# MEM.net
KiCad netlist of a schematic drawn in Altium Designer
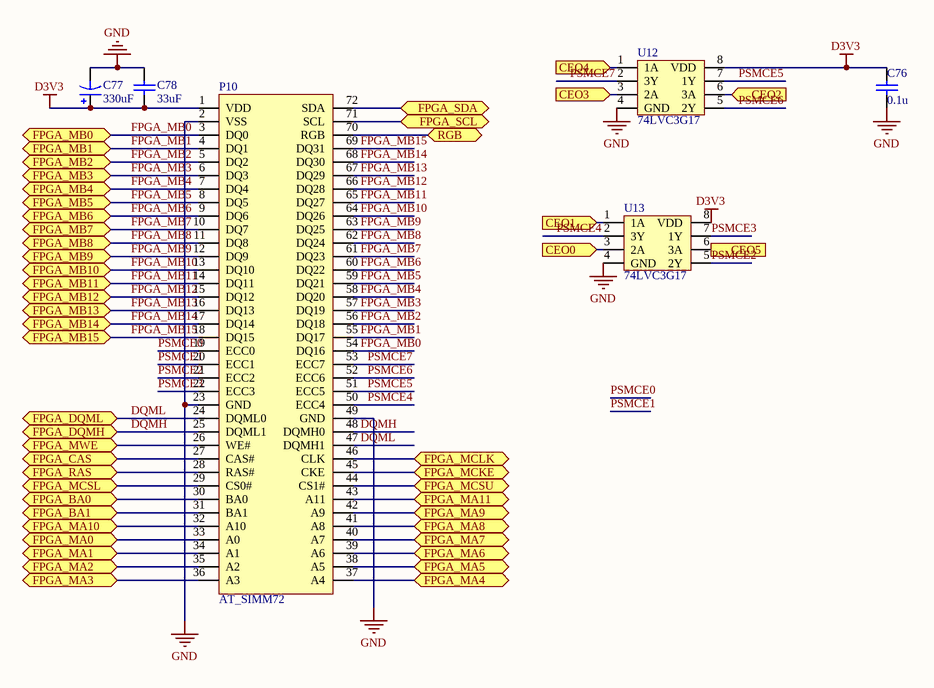
[diagram p0: MEM.SchDoc]

(export (version "E")
  (design (tool "Eeschema 10.0.6"))
  (components
    (comp (ref "C76")
      (value "0.1u")
      (footprint "0603C")
      (description "Capacitor")
      (fields (field (name "Comment") "Cap") (field (name "PUBLISHER") "Altium Limited"))
      (libsource (lib "Miscellaneous Devices") (part "Cap"))
    )
    (comp (ref "C77")
      (value "330uF")
      (footprint "TanCap-1210")
      (description "Polarized Capacitor (Radial)")
      (fields (field (name "Comment") "330u") (field (name "PUBLISHER") "Altium Limited"))
      (libsource (lib "Miscellaneous Devices") (part "Cap Pol1"))
    )
    (comp (ref "C78")
      (value "33uF")
      (footprint "0603C")
      (description "Ceramic Capacitor 0603")
      (fields (field (name "Comment") "106") (field (name "PUBLISHER") "Altium Limited"))
      (libsource (lib "Miscellaneous Devices") (part "Cap"))
    )
    (comp (ref "P10")
      (value "AT_SIMM72")
      (footprint "ATSIMM72")
      (libsource (lib "RV_AT_Ports") (part "AT_SIMM72"))
    )
    (comp (ref "U12")
      (value "74LVC3G17")
      (footprint "TSSOP-8N_3x3")
      (libsource (lib "74xLogic") (part "74LVC3G17"))
    )
    (comp (ref "U13")
      (value "74LVC3G17")
      (footprint "TSSOP-8N_3x3")
      (libsource (lib "74xLogic") (part "74LVC3G17"))
    )
  )
  (nets
    (net (code "1") (name "/CEO0") (class "Default")
      (node (ref "U13") (pin "3") (pinfunction "2A_3") (pintype "passive"))
    )
    (net (code "2") (name "/CEO1") (class "Default")
      (node (ref "U13") (pin "1") (pinfunction "1A_1") (pintype "passive"))
    )
    (net (code "3") (name "/CEO2") (class "Default")
      (node (ref "U12") (pin "6") (pinfunction "3A_6") (pintype "passive"))
    )
    (net (code "4") (name "/CEO3") (class "Default")
      (node (ref "U12") (pin "3") (pinfunction "2A_3") (pintype "passive"))
    )
    (net (code "5") (name "/CEO4") (class "Default")
      (node (ref "U12") (pin "1") (pinfunction "1A_1") (pintype "passive"))
    )
    (net (code "6") (name "/CEO5") (class "Default")
      (node (ref "U13") (pin "6") (pinfunction "3A_6") (pintype "passive"))
    )
    (net (code "7") (name "/DQMH") (class "Default")
      (node (ref "P10") (pin "25") (pinfunction "DQML1_25") (pintype "passive"))
      (node (ref "P10") (pin "48") (pinfunction "DQMH0_48") (pintype "passive"))
    )
    (net (code "8") (name "/DQML") (class "Default")
      (node (ref "P10") (pin "24") (pinfunction "DQML0_24") (pintype "passive"))
      (node (ref "P10") (pin "47") (pinfunction "DQMH1_47") (pintype "passive"))
    )
    (net (code "9") (name "/FPGA_BA0") (class "Default")
      (node (ref "P10") (pin "30") (pinfunction "BA0_30") (pintype "passive"))
    )
    (net (code "10") (name "/FPGA_BA1") (class "Default")
      (node (ref "P10") (pin "31") (pinfunction "BA1_31") (pintype "passive"))
    )
    (net (code "11") (name "/FPGA_CAS") (class "Default")
      (node (ref "P10") (pin "27") (pinfunction "CAS#_27") (pintype "passive"))
    )
    (net (code "12") (name "/FPGA_MA0") (class "Default")
      (node (ref "P10") (pin "33") (pinfunction "A0_33") (pintype "passive"))
    )
    (net (code "13") (name "/FPGA_MA1") (class "Default")
      (node (ref "P10") (pin "34") (pinfunction "A1_34") (pintype "passive"))
    )
    (net (code "14") (name "/FPGA_MA2") (class "Default")
      (node (ref "P10") (pin "35") (pinfunction "A2_35") (pintype "passive"))
    )
    (net (code "15") (name "/FPGA_MA3") (class "Default")
      (node (ref "P10") (pin "36") (pinfunction "A3_36") (pintype "passive"))
    )
    (net (code "16") (name "/FPGA_MA4") (class "Default")
      (node (ref "P10") (pin "37") (pinfunction "A4_37") (pintype "passive"))
    )
    (net (code "17") (name "/FPGA_MA5") (class "Default")
      (node (ref "P10") (pin "38") (pinfunction "A5_38") (pintype "passive"))
    )
    (net (code "18") (name "/FPGA_MA6") (class "Default")
      (node (ref "P10") (pin "39") (pinfunction "A6_39") (pintype "passive"))
    )
    (net (code "19") (name "/FPGA_MA7") (class "Default")
      (node (ref "P10") (pin "40") (pinfunction "A7_40") (pintype "passive"))
    )
    (net (code "20") (name "/FPGA_MA8") (class "Default")
      (node (ref "P10") (pin "41") (pinfunction "A8_41") (pintype "passive"))
    )
    (net (code "21") (name "/FPGA_MA9") (class "Default")
      (node (ref "P10") (pin "42") (pinfunction "A9_42") (pintype "passive"))
    )
    (net (code "22") (name "/FPGA_MA10") (class "Default")
      (node (ref "P10") (pin "32") (pinfunction "A10_32") (pintype "passive"))
    )
    (net (code "23") (name "/FPGA_MA11") (class "Default")
      (node (ref "P10") (pin "43") (pinfunction "A11_43") (pintype "passive"))
    )
    (net (code "24") (name "/FPGA_MB0") (class "Default")
      (node (ref "P10") (pin "3") (pinfunction "DQ0_3") (pintype "passive"))
      (node (ref "P10") (pin "54") (pinfunction "DQ16_54") (pintype "passive"))
    )
    (net (code "25") (name "/FPGA_MB1") (class "Default")
      (node (ref "P10") (pin "4") (pinfunction "DQ1_4") (pintype "passive"))
      (node (ref "P10") (pin "55") (pinfunction "DQ17_55") (pintype "passive"))
    )
    (net (code "26") (name "/FPGA_MB2") (class "Default")
      (node (ref "P10") (pin "5") (pinfunction "DQ2_5") (pintype "passive"))
      (node (ref "P10") (pin "56") (pinfunction "DQ18_56") (pintype "passive"))
    )
    (net (code "27") (name "/FPGA_MB3") (class "Default")
      (node (ref "P10") (pin "57") (pinfunction "DQ19_57") (pintype "passive"))
      (node (ref "P10") (pin "6") (pinfunction "DQ3_6") (pintype "passive"))
    )
    (net (code "28") (name "/FPGA_MB4") (class "Default")
      (node (ref "P10") (pin "58") (pinfunction "DQ20_58") (pintype "passive"))
      (node (ref "P10") (pin "7") (pinfunction "DQ4_7") (pintype "passive"))
    )
    (net (code "29") (name "/FPGA_MB5") (class "Default")
      (node (ref "P10") (pin "59") (pinfunction "DQ21_59") (pintype "passive"))
      (node (ref "P10") (pin "8") (pinfunction "DQ5_8") (pintype "passive"))
    )
    (net (code "30") (name "/FPGA_MB6") (class "Default")
      (node (ref "P10") (pin "60") (pinfunction "DQ22_60") (pintype "passive"))
      (node (ref "P10") (pin "9") (pinfunction "DQ6_9") (pintype "passive"))
    )
    (net (code "31") (name "/FPGA_MB7") (class "Default")
      (node (ref "P10") (pin "10") (pinfunction "DQ7_10") (pintype "passive"))
      (node (ref "P10") (pin "61") (pinfunction "DQ23_61") (pintype "passive"))
    )
    (net (code "32") (name "/FPGA_MB8") (class "Default")
      (node (ref "P10") (pin "11") (pinfunction "DQ8_11") (pintype "passive"))
      (node (ref "P10") (pin "62") (pinfunction "DQ24_62") (pintype "passive"))
    )
    (net (code "33") (name "/FPGA_MB9") (class "Default")
      (node (ref "P10") (pin "12") (pinfunction "DQ9_12") (pintype "passive"))
      (node (ref "P10") (pin "63") (pinfunction "DQ25_63") (pintype "passive"))
    )
    (net (code "34") (name "/FPGA_MB10") (class "Default")
      (node (ref "P10") (pin "13") (pinfunction "DQ10_13") (pintype "passive"))
      (node (ref "P10") (pin "64") (pinfunction "DQ26_64") (pintype "passive"))
    )
    (net (code "35") (name "/FPGA_MB11") (class "Default")
      (node (ref "P10") (pin "14") (pinfunction "DQ11_14") (pintype "passive"))
      (node (ref "P10") (pin "65") (pinfunction "DQ27_65") (pintype "passive"))
    )
    (net (code "36") (name "/FPGA_MB12") (class "Default")
      (node (ref "P10") (pin "15") (pinfunction "DQ12_15") (pintype "passive"))
      (node (ref "P10") (pin "66") (pinfunction "DQ28_66") (pintype "passive"))
    )
    (net (code "37") (name "/FPGA_MB13") (class "Default")
      (node (ref "P10") (pin "16") (pinfunction "DQ13_16") (pintype "passive"))
      (node (ref "P10") (pin "67") (pinfunction "DQ29_67") (pintype "passive"))
    )
    (net (code "38") (name "/FPGA_MB14") (class "Default")
      (node (ref "P10") (pin "17") (pinfunction "DQ14_17") (pintype "passive"))
      (node (ref "P10") (pin "68") (pinfunction "DQ30_68") (pintype "passive"))
    )
    (net (code "39") (name "/FPGA_MB15") (class "Default")
      (node (ref "P10") (pin "18") (pinfunction "DQ15_18") (pintype "passive"))
      (node (ref "P10") (pin "69") (pinfunction "DQ31_69") (pintype "passive"))
    )
    (net (code "40") (name "/FPGA_MCKE") (class "Default")
      (node (ref "P10") (pin "45") (pinfunction "CKE_45") (pintype "passive"))
    )
    (net (code "41") (name "/FPGA_MCLK") (class "Default")
      (node (ref "P10") (pin "46") (pinfunction "CLK_46") (pintype "passive"))
    )
    (net (code "42") (name "/FPGA_MCSL") (class "Default")
      (node (ref "P10") (pin "29") (pinfunction "CS0#_29") (pintype "passive"))
    )
    (net (code "43") (name "/FPGA_MCSU") (class "Default")
      (node (ref "P10") (pin "44") (pinfunction "CS1#_44") (pintype "passive"))
    )
    (net (code "44") (name "/FPGA_MWE") (class "Default")
      (node (ref "P10") (pin "26") (pinfunction "WE#_26") (pintype "passive"))
    )
    (net (code "45") (name "/FPGA_RAS") (class "Default")
      (node (ref "P10") (pin "28") (pinfunction "RAS#_28") (pintype "passive"))
    )
    (net (code "46") (name "/FPGA_SCL") (class "Default")
      (node (ref "P10") (pin "71") (pinfunction "SCL_71") (pintype "passive"))
    )
    (net (code "47") (name "/FPGA_SDA") (class "Default")
      (node (ref "P10") (pin "72") (pinfunction "SDA_72") (pintype "passive"))
    )
    (net (code "48") (name "/PSMCE0") (class "Default")
      (node (ref "P10") (pin "19") (pinfunction "ECC0_19") (pintype "passive"))
    )
    (net (code "49") (name "/PSMCE1") (class "Default")
      (node (ref "P10") (pin "20") (pinfunction "ECC1_20") (pintype "passive"))
    )
    (net (code "50") (name "/PSMCE2") (class "Default")
      (node (ref "P10") (pin "21") (pinfunction "ECC2_21") (pintype "passive"))
      (node (ref "U13") (pin "5") (pinfunction "2Y_5") (pintype "passive"))
    )
    (net (code "51") (name "/PSMCE3") (class "Default")
      (node (ref "P10") (pin "22") (pinfunction "ECC3_22") (pintype "passive"))
      (node (ref "U13") (pin "7") (pinfunction "1Y_7") (pintype "passive"))
    )
    (net (code "52") (name "/PSMCE4") (class "Default")
      (node (ref "P10") (pin "50") (pinfunction "ECC4_50") (pintype "passive"))
      (node (ref "U13") (pin "2") (pinfunction "3Y_2") (pintype "passive"))
    )
    (net (code "53") (name "/PSMCE5") (class "Default")
      (node (ref "P10") (pin "51") (pinfunction "ECC5_51") (pintype "passive"))
      (node (ref "U12") (pin "7") (pinfunction "1Y_7") (pintype "passive"))
    )
    (net (code "54") (name "/PSMCE6") (class "Default")
      (node (ref "P10") (pin "52") (pinfunction "ECC6_52") (pintype "passive"))
      (node (ref "U12") (pin "5") (pinfunction "2Y_5") (pintype "passive"))
    )
    (net (code "55") (name "/PSMCE7") (class "Default")
      (node (ref "P10") (pin "53") (pinfunction "ECC7_53") (pintype "passive"))
      (node (ref "U12") (pin "2") (pinfunction "3Y_2") (pintype "passive"))
    )
    (net (code "56") (name "/RGB") (class "Default")
      (node (ref "P10") (pin "70") (pinfunction "RGB_70") (pintype "passive"))
    )
    (net (code "57") (name "D3V3") (class "Default")
      (node (ref "C76") (pin "2") (pinfunction "2_2") (pintype "passive"))
      (node (ref "C77") (pin "1") (pinfunction "1_1") (pintype "passive"))
      (node (ref "C78") (pin "2") (pinfunction "2_2") (pintype "passive"))
      (node (ref "P10") (pin "1") (pinfunction "VDD_1") (pintype "passive"))
      (node (ref "U12") (pin "8") (pinfunction "VDD_8") (pintype "passive"))
      (node (ref "U13") (pin "8") (pinfunction "VDD_8") (pintype "passive"))
    )
    (net (code "58") (name "GND") (class "Default")
      (node (ref "C76") (pin "1") (pinfunction "1_1") (pintype "passive"))
      (node (ref "C77") (pin "2") (pinfunction "2_2") (pintype "passive"))
      (node (ref "C78") (pin "1") (pinfunction "1_1") (pintype "passive"))
      (node (ref "P10") (pin "2") (pinfunction "VSS_2") (pintype "passive"))
      (node (ref "P10") (pin "23") (pinfunction "GND_23") (pintype "passive"))
      (node (ref "P10") (pin "49") (pinfunction "GND_49") (pintype "passive"))
      (node (ref "U12") (pin "4") (pinfunction "GND_4") (pintype "passive"))
      (node (ref "U13") (pin "4") (pinfunction "GND_4") (pintype "passive"))
    )
  )
)
